# untitled.net
KiCad netlist of a schematic drawn in EAGLE
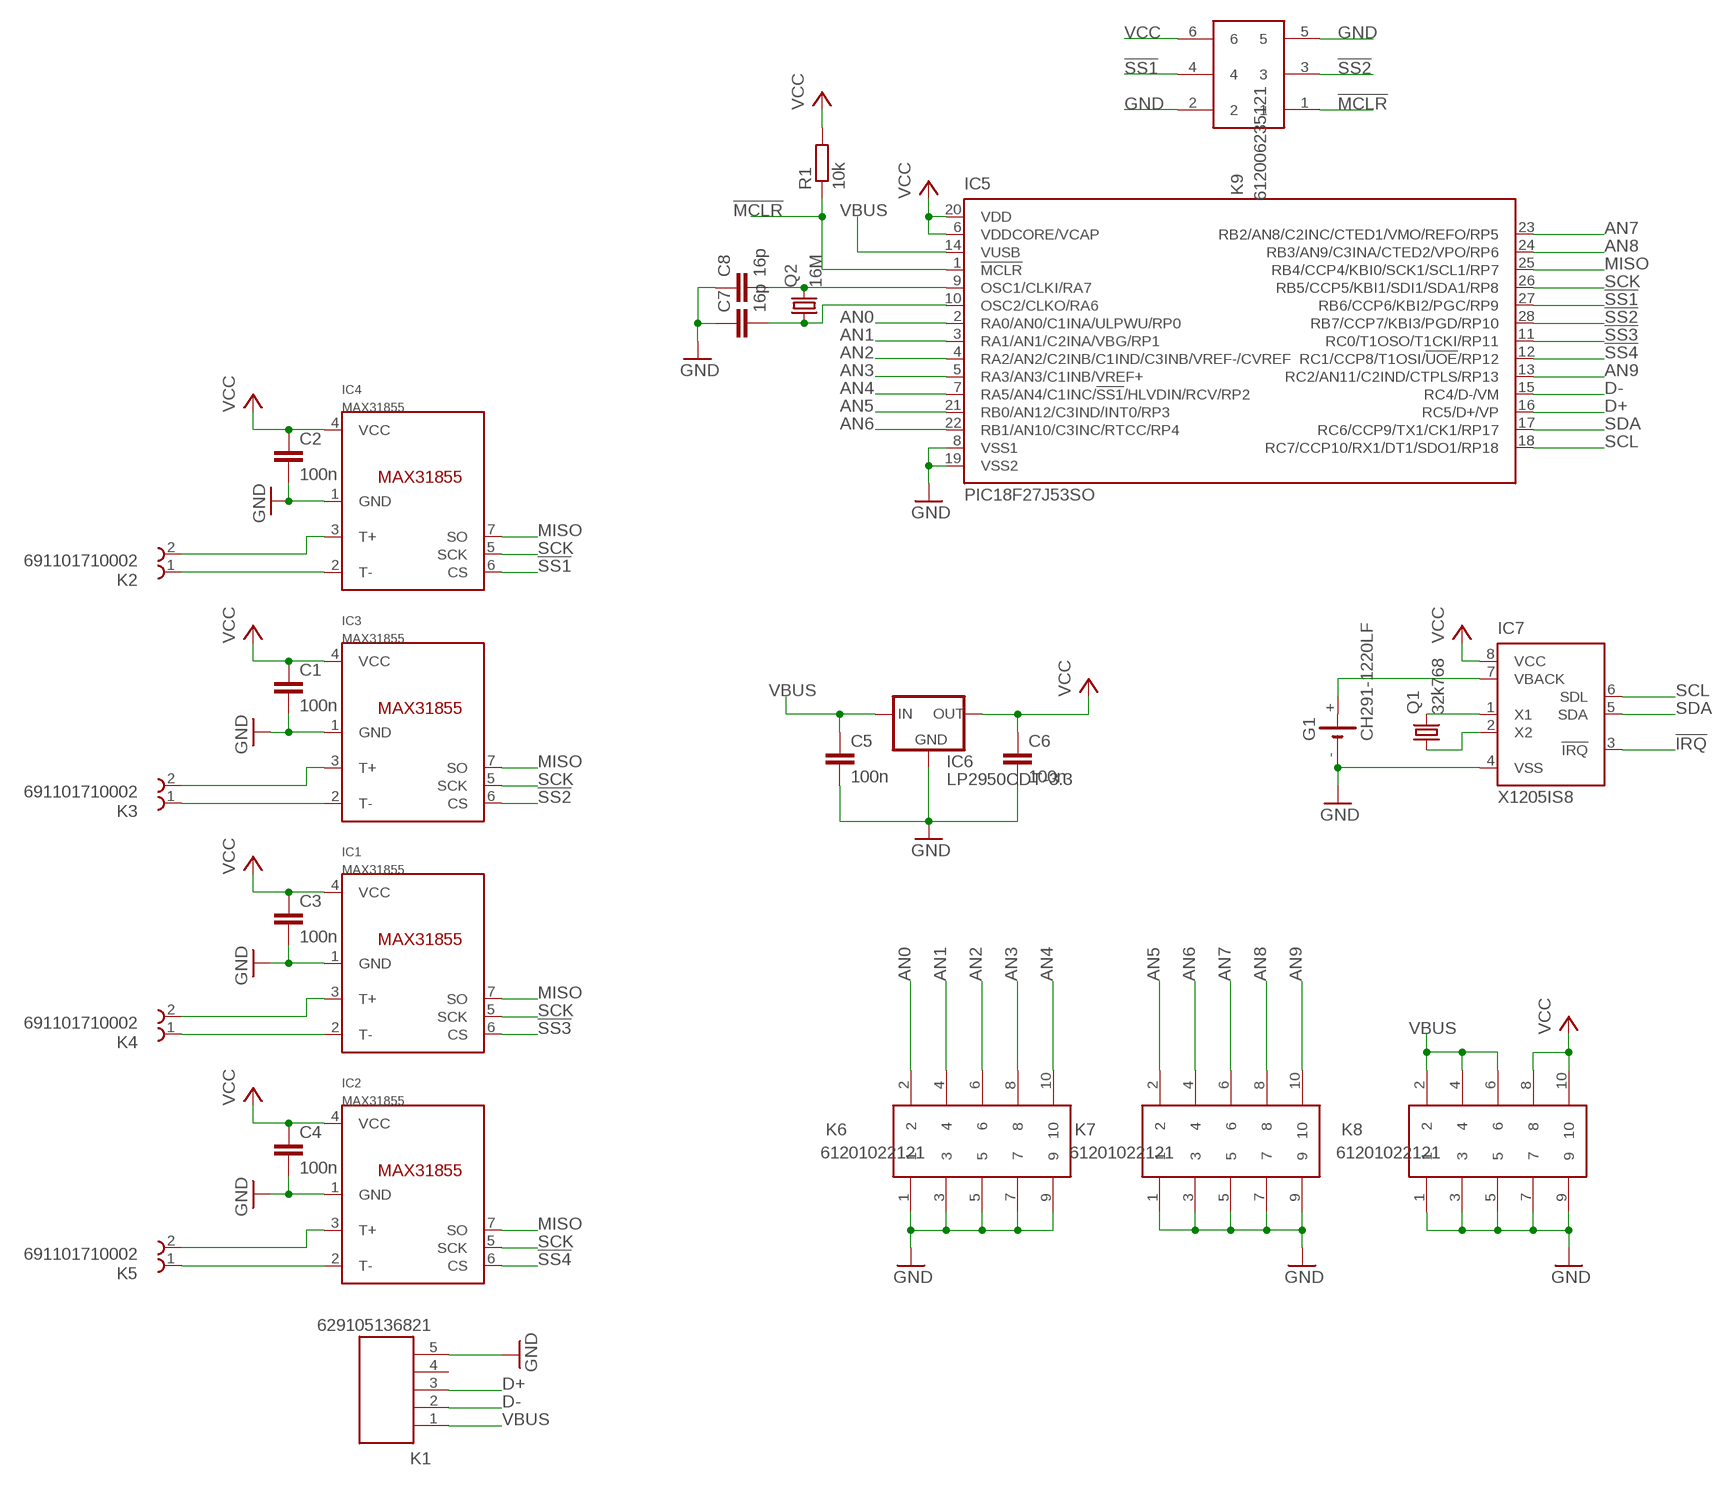
[diagram p0: schematic, sheet 1]

(export (version "E")
  (design (tool "Eeschema 10.0.6"))
  (components
    (comp (ref "C1")
      (value "100n")
      (footprint "eagle-import:C1206")
      (libsource (lib "eagle-import") (part "C-EUC1206"))
    )
    (comp (ref "C2")
      (value "100n")
      (footprint "eagle-import:C1206")
      (libsource (lib "eagle-import") (part "C-EUC1206"))
    )
    (comp (ref "C3")
      (value "100n")
      (footprint "eagle-import:C1206")
      (libsource (lib "eagle-import") (part "C-EUC1206"))
    )
    (comp (ref "C4")
      (value "100n")
      (footprint "eagle-import:C1206")
      (libsource (lib "eagle-import") (part "C-EUC1206"))
    )
    (comp (ref "C5")
      (value "100n")
      (footprint "eagle-import:C1206")
      (libsource (lib "eagle-import") (part "C-EUC1206"))
    )
    (comp (ref "C6")
      (value "100n")
      (footprint "eagle-import:C1206")
      (libsource (lib "eagle-import") (part "C-EUC1206"))
    )
    (comp (ref "C7")
      (value "16p")
      (footprint "eagle-import:C0805")
      (libsource (lib "eagle-import") (part "C-EUC0805"))
    )
    (comp (ref "C8")
      (value "16p")
      (footprint "eagle-import:C0805")
      (libsource (lib "eagle-import") (part "C-EUC0805"))
    )
    (comp (ref "G1")
      (value "CH291-1220LF")
      (footprint "eagle-import:CH291-1220LF")
      (libsource (lib "eagle-import") (part "CH291-1220LF"))
    )
    (comp (ref "IC1")
      (value "MAX31855")
      (footprint "eagle-import:SOIC8")
      (libsource (lib "eagle-import") (part "MAX31855"))
    )
    (comp (ref "IC2")
      (value "MAX31855")
      (footprint "eagle-import:SOIC8")
      (libsource (lib "eagle-import") (part "MAX31855"))
    )
    (comp (ref "IC3")
      (value "MAX31855")
      (footprint "eagle-import:SOIC8")
      (libsource (lib "eagle-import") (part "MAX31855"))
    )
    (comp (ref "IC4")
      (value "MAX31855")
      (footprint "eagle-import:SOIC8")
      (libsource (lib "eagle-import") (part "MAX31855"))
    )
    (comp (ref "IC5")
      (value "PIC18F27J53SO")
      (footprint "eagle-import:SO28W")
      (fields (field (name "MPN") "PIC18F27J53-I/SO"))
      (libsource (lib "eagle-import") (part "PIC18F2J53SO7"))
    )
    (comp (ref "IC6")
      (value "LP2950CDT-3.3")
      (footprint "eagle-import:DPACK")
      (libsource (lib "eagle-import") (part "LP2950?CDT-3.3"))
    )
    (comp (ref "IC7")
      (value "X1205IS8")
      (footprint "eagle-import:SO-08")
      (libsource (lib "eagle-import") (part "X1205S8I"))
    )
    (comp (ref "K1")
      (value "629105136821")
      (footprint "eagle-import:629105136821")
      (libsource (lib "eagle-import") (part "629105136821"))
    )
    (comp (ref "K2")
      (value "691101710002")
      (footprint "eagle-import:691101710002")
      (libsource (lib "eagle-import") (part "691101710002"))
    )
    (comp (ref "K3")
      (value "691101710002")
      (footprint "eagle-import:691101710002")
      (libsource (lib "eagle-import") (part "691101710002"))
    )
    (comp (ref "K4")
      (value "691101710002")
      (footprint "eagle-import:691101710002")
      (libsource (lib "eagle-import") (part "691101710002"))
    )
    (comp (ref "K5")
      (value "691101710002")
      (footprint "eagle-import:691101710002")
      (libsource (lib "eagle-import") (part "691101710002"))
    )
    (comp (ref "K6")
      (value "61201022121")
      (footprint "eagle-import:61201022121")
      (libsource (lib "eagle-import") (part "61201022121"))
    )
    (comp (ref "K7")
      (value "61201022121")
      (footprint "eagle-import:61201022121")
      (libsource (lib "eagle-import") (part "61201022121"))
    )
    (comp (ref "K8")
      (value "61201022121")
      (footprint "eagle-import:61201022121")
      (libsource (lib "eagle-import") (part "61201022121"))
    )
    (comp (ref "K9")
      (value "612006235121")
      (footprint "eagle-import:612006235121")
      (libsource (lib "eagle-import") (part "612006235121"))
    )
    (comp (ref "Q1")
      (value "32k768")
      (footprint "eagle-import:TC26H")
      (libsource (lib "eagle-import") (part "CRYSTALTC26H"))
    )
    (comp (ref "Q2")
      (value "16M")
      (footprint "eagle-import:CTS406")
      (libsource (lib "eagle-import") (part "CRYSTALCTS406"))
    )
    (comp (ref "R1")
      (value "10k")
      (footprint "eagle-import:M1206")
      (libsource (lib "eagle-import") (part "R-EU_M1206"))
    )
  )
  (nets
    (net (code "1") (name "/AN0") (class "Default")
      (node (ref "IC5") (pin "2") (pinfunction "RA0/AN0/C1INA/ULPWU/RP0_2") (pintype "bidirectional"))
      (node (ref "K6") (pin "2") (pinfunction "2_2") (pintype "passive"))
    )
    (net (code "2") (name "/AN1") (class "Default")
      (node (ref "IC5") (pin "3") (pinfunction "RA1/AN1/C2INA/VBG/RP1_3") (pintype "bidirectional"))
      (node (ref "K6") (pin "4") (pinfunction "4_4") (pintype "passive"))
    )
    (net (code "3") (name "/AN2") (class "Default")
      (node (ref "IC5") (pin "4") (pinfunction "RA2/AN2/C2INB/C1IND/C3INB/VREF-/CVREF_4") (pintype "bidirectional"))
      (node (ref "K6") (pin "6") (pinfunction "6_6") (pintype "passive"))
    )
    (net (code "4") (name "/AN3") (class "Default")
      (node (ref "IC5") (pin "5") (pinfunction "RA3/AN3/C1INB/VREF+_5") (pintype "bidirectional"))
      (node (ref "K6") (pin "8") (pinfunction "8_8") (pintype "passive"))
    )
    (net (code "5") (name "/AN4") (class "Default")
      (node (ref "IC5") (pin "7") (pinfunction "RA5/AN4/C1INC/~{SS1}/HLVDIN/RCV/RP2_7") (pintype "bidirectional"))
      (node (ref "K6") (pin "10") (pinfunction "10_10") (pintype "passive"))
    )
    (net (code "6") (name "/AN5") (class "Default")
      (node (ref "IC5") (pin "21") (pinfunction "RB0/AN12/C3IND/INT0/RP3_21") (pintype "bidirectional"))
      (node (ref "K7") (pin "2") (pinfunction "2_2") (pintype "passive"))
    )
    (net (code "7") (name "/AN6") (class "Default")
      (node (ref "IC5") (pin "22") (pinfunction "RB1/AN10/C3INC/RTCC/RP4_22") (pintype "bidirectional"))
      (node (ref "K7") (pin "4") (pinfunction "4_4") (pintype "passive"))
    )
    (net (code "8") (name "/AN7") (class "Default")
      (node (ref "IC5") (pin "23") (pinfunction "RB2/AN8/C2INC/CTED1/VMO/REFO/RP5_23") (pintype "bidirectional"))
      (node (ref "K7") (pin "6") (pinfunction "6_6") (pintype "passive"))
    )
    (net (code "9") (name "/AN8") (class "Default")
      (node (ref "IC5") (pin "24") (pinfunction "RB3/AN9/C3INA/CTED2/VPO/RP6_24") (pintype "bidirectional"))
      (node (ref "K7") (pin "8") (pinfunction "8_8") (pintype "passive"))
    )
    (net (code "10") (name "/AN9") (class "Default")
      (node (ref "IC5") (pin "13") (pinfunction "RC2/AN11/C2IND/CTPLS/RP13_13") (pintype "bidirectional"))
      (node (ref "K7") (pin "10") (pinfunction "10_10") (pintype "passive"))
    )
    (net (code "11") (name "/D+") (class "Default")
      (node (ref "IC5") (pin "16") (pinfunction "RC5/D+/VP_16") (pintype "bidirectional"))
      (node (ref "K1") (pin "3") (pinfunction "3_3") (pintype "passive"))
    )
    (net (code "12") (name "/D-") (class "Default")
      (node (ref "IC5") (pin "15") (pinfunction "RC4/D-/VM_15") (pintype "bidirectional"))
      (node (ref "K1") (pin "2") (pinfunction "2_2") (pintype "passive"))
    )
    (net (code "13") (name "/MISO") (class "Default")
      (node (ref "IC1") (pin "7") (pinfunction "SO_7") (pintype "output"))
      (node (ref "IC2") (pin "7") (pinfunction "SO_7") (pintype "output"))
      (node (ref "IC3") (pin "7") (pinfunction "SO_7") (pintype "output"))
      (node (ref "IC4") (pin "7") (pinfunction "SO_7") (pintype "output"))
      (node (ref "IC5") (pin "25") (pinfunction "RB4/CCP4/KBI0/SCK1/SCL1/RP7_25") (pintype "bidirectional"))
    )
    (net (code "14") (name "/SCK") (class "Default")
      (node (ref "IC1") (pin "5") (pinfunction "SCK_5") (pintype "input"))
      (node (ref "IC2") (pin "5") (pinfunction "SCK_5") (pintype "input"))
      (node (ref "IC3") (pin "5") (pinfunction "SCK_5") (pintype "input"))
      (node (ref "IC4") (pin "5") (pinfunction "SCK_5") (pintype "input"))
      (node (ref "IC5") (pin "26") (pinfunction "RB5/CCP5/KBI1/SDI1/SDA1/RP8_26") (pintype "bidirectional"))
    )
    (net (code "15") (name "/SCL") (class "Default")
      (node (ref "IC5") (pin "18") (pinfunction "RC7/CCP10/RX1/DT1/SDO1/RP18_18") (pintype "bidirectional"))
      (node (ref "IC7") (pin "6") (pinfunction "SDL_6") (pintype "input"))
    )
    (net (code "16") (name "/SDA") (class "Default")
      (node (ref "IC5") (pin "17") (pinfunction "RC6/CCP9/TX1/CK1/RP17_17") (pintype "bidirectional"))
      (node (ref "IC7") (pin "5") (pinfunction "SDA_5") (pintype "bidirectional"))
    )
    (net (code "17") (name "/VBUS") (class "Default")
      (node (ref "C5") (pin "1") (pinfunction "1_1") (pintype "passive"))
      (node (ref "IC5") (pin "14") (pinfunction "VUSB_14") (pintype "input"))
      (node (ref "IC6") (pin "1") (pinfunction "IN_1") (pintype "input"))
      (node (ref "K1") (pin "1") (pinfunction "1_1") (pintype "passive"))
      (node (ref "K8") (pin "2") (pinfunction "2_2") (pintype "passive"))
      (node (ref "K8") (pin "4") (pinfunction "4_4") (pintype "passive"))
      (node (ref "K8") (pin "6") (pinfunction "6_6") (pintype "passive"))
    )
    (net (code "18") (name "/~{IRQ}") (class "Default")
      (node (ref "IC7") (pin "3") (pinfunction "~{IRQ}_3") (pintype "output"))
    )
    (net (code "19") (name "/~{MCLR}") (class "Default")
      (node (ref "IC5") (pin "1") (pinfunction "~{MCLR}_1") (pintype "input"))
      (node (ref "K9") (pin "1") (pinfunction "1_1") (pintype "passive"))
      (node (ref "R1") (pin "1") (pinfunction "1_1") (pintype "passive"))
    )
    (net (code "20") (name "/~{SS1}") (class "Default")
      (node (ref "IC4") (pin "6") (pinfunction "CS_6") (pintype "input"))
      (node (ref "IC5") (pin "27") (pinfunction "RB6/CCP6/KBI2/PGC/RP9_27") (pintype "bidirectional"))
      (node (ref "K9") (pin "4") (pinfunction "4_4") (pintype "passive"))
    )
    (net (code "21") (name "/~{SS2}") (class "Default")
      (node (ref "IC3") (pin "6") (pinfunction "CS_6") (pintype "input"))
      (node (ref "IC5") (pin "28") (pinfunction "RB7/CCP7/KBI3/PGD/RP10_28") (pintype "bidirectional"))
      (node (ref "K9") (pin "3") (pinfunction "3_3") (pintype "passive"))
    )
    (net (code "22") (name "/~{SS3}") (class "Default")
      (node (ref "IC1") (pin "6") (pinfunction "CS_6") (pintype "input"))
      (node (ref "IC5") (pin "11") (pinfunction "RC0/T1OSO/T1CKI/RP11_11") (pintype "bidirectional"))
    )
    (net (code "23") (name "/~{SS4}") (class "Default")
      (node (ref "IC2") (pin "6") (pinfunction "CS_6") (pintype "input"))
      (node (ref "IC5") (pin "12") (pinfunction "RC1/CCP8/T1OSI/~{UOE}/RP12_12") (pintype "bidirectional"))
    )
    (net (code "24") (name "GND") (class "Default")
      (node (ref "C1") (pin "2") (pinfunction "2_2") (pintype "passive"))
      (node (ref "C2") (pin "2") (pinfunction "2_2") (pintype "passive"))
      (node (ref "C3") (pin "2") (pinfunction "2_2") (pintype "passive"))
      (node (ref "C4") (pin "2") (pinfunction "2_2") (pintype "passive"))
      (node (ref "C5") (pin "2") (pinfunction "2_2") (pintype "passive"))
      (node (ref "C6") (pin "2") (pinfunction "2_2") (pintype "passive"))
      (node (ref "C7") (pin "1") (pinfunction "1_1") (pintype "passive"))
      (node (ref "C8") (pin "1") (pinfunction "1_1") (pintype "passive"))
      (node (ref "G1") (pin "-") (pinfunction "-_-") (pintype "passive"))
      (node (ref "IC1") (pin "1") (pinfunction "GND_1") (pintype "power_in"))
      (node (ref "IC2") (pin "1") (pinfunction "GND_1") (pintype "power_in"))
      (node (ref "IC3") (pin "1") (pinfunction "GND_1") (pintype "power_in"))
      (node (ref "IC4") (pin "1") (pinfunction "GND_1") (pintype "power_in"))
      (node (ref "IC5") (pin "19") (pinfunction "VSS2_19") (pintype "input"))
      (node (ref "IC5") (pin "8") (pinfunction "VSS1_8") (pintype "input"))
      (node (ref "IC6") (pin "4") (pinfunction "GND_4") (pintype "input"))
      (node (ref "IC7") (pin "4") (pinfunction "VSS_4") (pintype "power_in"))
      (node (ref "K1") (pin "5") (pinfunction "5_5") (pintype "passive"))
      (node (ref "K6") (pin "1") (pinfunction "1_1") (pintype "passive"))
      (node (ref "K6") (pin "3") (pinfunction "3_3") (pintype "passive"))
      (node (ref "K6") (pin "5") (pinfunction "5_5") (pintype "passive"))
      (node (ref "K6") (pin "7") (pinfunction "7_7") (pintype "passive"))
      (node (ref "K6") (pin "9") (pinfunction "9_9") (pintype "passive"))
      (node (ref "K7") (pin "1") (pinfunction "1_1") (pintype "passive"))
      (node (ref "K7") (pin "3") (pinfunction "3_3") (pintype "passive"))
      (node (ref "K7") (pin "5") (pinfunction "5_5") (pintype "passive"))
      (node (ref "K7") (pin "7") (pinfunction "7_7") (pintype "passive"))
      (node (ref "K7") (pin "9") (pinfunction "9_9") (pintype "passive"))
      (node (ref "K8") (pin "1") (pinfunction "1_1") (pintype "passive"))
      (node (ref "K8") (pin "3") (pinfunction "3_3") (pintype "passive"))
      (node (ref "K8") (pin "5") (pinfunction "5_5") (pintype "passive"))
      (node (ref "K8") (pin "7") (pinfunction "7_7") (pintype "passive"))
      (node (ref "K8") (pin "9") (pinfunction "9_9") (pintype "passive"))
      (node (ref "K9") (pin "2") (pinfunction "2_2") (pintype "passive"))
      (node (ref "K9") (pin "5") (pinfunction "5_5") (pintype "passive"))
    )
    (net (code "25") (name "Net-(IC1-T+)") (class "Default")
      (node (ref "IC1") (pin "3") (pinfunction "T+_3") (pintype "input"))
      (node (ref "K4") (pin "2") (pinfunction "2_2") (pintype "passive"))
    )
    (net (code "26") (name "Net-(IC1-T-)") (class "Default")
      (node (ref "IC1") (pin "2") (pinfunction "T-_2") (pintype "input"))
      (node (ref "K4") (pin "1") (pinfunction "1_1") (pintype "passive"))
    )
    (net (code "27") (name "Net-(IC2-T+)") (class "Default")
      (node (ref "IC2") (pin "3") (pinfunction "T+_3") (pintype "input"))
      (node (ref "K5") (pin "2") (pinfunction "2_2") (pintype "passive"))
    )
    (net (code "28") (name "Net-(IC2-T-)") (class "Default")
      (node (ref "IC2") (pin "2") (pinfunction "T-_2") (pintype "input"))
      (node (ref "K5") (pin "1") (pinfunction "1_1") (pintype "passive"))
    )
    (net (code "29") (name "Net-(IC3-T+)") (class "Default")
      (node (ref "IC3") (pin "3") (pinfunction "T+_3") (pintype "input"))
      (node (ref "K3") (pin "2") (pinfunction "2_2") (pintype "passive"))
    )
    (net (code "30") (name "Net-(IC3-T-)") (class "Default")
      (node (ref "IC3") (pin "2") (pinfunction "T-_2") (pintype "input"))
      (node (ref "K3") (pin "1") (pinfunction "1_1") (pintype "passive"))
    )
    (net (code "31") (name "Net-(IC4-T+)") (class "Default")
      (node (ref "IC4") (pin "3") (pinfunction "T+_3") (pintype "input"))
      (node (ref "K2") (pin "2") (pinfunction "2_2") (pintype "passive"))
    )
    (net (code "32") (name "Net-(IC4-T-)") (class "Default")
      (node (ref "IC4") (pin "2") (pinfunction "T-_2") (pintype "input"))
      (node (ref "K2") (pin "1") (pinfunction "1_1") (pintype "passive"))
    )
    (net (code "33") (name "Net-(IC5-OSC1{slash}CLKI{slash}RA7)") (class "Default")
      (node (ref "C8") (pin "2") (pinfunction "2_2") (pintype "passive"))
      (node (ref "IC5") (pin "9") (pinfunction "OSC1/CLKI/RA7_9") (pintype "bidirectional"))
      (node (ref "Q2") (pin "3") (pinfunction "2_3") (pintype "passive"))
    )
    (net (code "34") (name "Net-(IC5-OSC2{slash}CLKO{slash}RA6)") (class "Default")
      (node (ref "C7") (pin "2") (pinfunction "2_2") (pintype "passive"))
      (node (ref "IC5") (pin "10") (pinfunction "OSC2/CLKO/RA6_10") (pintype "bidirectional"))
      (node (ref "Q2") (pin "1") (pinfunction "1_1") (pintype "passive"))
    )
    (net (code "35") (name "Net-(IC7-VBACK)") (class "Default")
      (node (ref "G1") (pin "+") (pinfunction "+_+") (pintype "passive"))
      (node (ref "IC7") (pin "7") (pinfunction "VBACK_7") (pintype "input"))
    )
    (net (code "36") (name "Net-(IC7-X1)") (class "Default")
      (node (ref "IC7") (pin "1") (pinfunction "X1_1") (pintype "input"))
      (node (ref "Q1") (pin "2") (pinfunction "2_2") (pintype "passive"))
    )
    (net (code "37") (name "Net-(IC7-X2)") (class "Default")
      (node (ref "IC7") (pin "2") (pinfunction "X2_2") (pintype "output"))
      (node (ref "Q1") (pin "1") (pinfunction "1_1") (pintype "passive"))
    )
    (net (code "38") (name "VCC") (class "Default")
      (node (ref "C1") (pin "1") (pinfunction "1_1") (pintype "passive"))
      (node (ref "C2") (pin "1") (pinfunction "1_1") (pintype "passive"))
      (node (ref "C3") (pin "1") (pinfunction "1_1") (pintype "passive"))
      (node (ref "C4") (pin "1") (pinfunction "1_1") (pintype "passive"))
      (node (ref "C6") (pin "1") (pinfunction "1_1") (pintype "passive"))
      (node (ref "IC1") (pin "4") (pinfunction "VCC_4") (pintype "power_in"))
      (node (ref "IC2") (pin "4") (pinfunction "VCC_4") (pintype "power_in"))
      (node (ref "IC3") (pin "4") (pinfunction "VCC_4") (pintype "power_in"))
      (node (ref "IC4") (pin "4") (pinfunction "VCC_4") (pintype "power_in"))
      (node (ref "IC5") (pin "20") (pinfunction "VDD_20") (pintype "input"))
      (node (ref "IC5") (pin "6") (pinfunction "VDDCORE/VCAP_6") (pintype "input"))
      (node (ref "IC6") (pin "3") (pinfunction "OUT_3") (pintype "passive"))
      (node (ref "IC7") (pin "8") (pinfunction "VCC_8") (pintype "power_in"))
      (node (ref "K8") (pin "10") (pinfunction "10_10") (pintype "passive"))
      (node (ref "K8") (pin "8") (pinfunction "8_8") (pintype "passive"))
      (node (ref "K9") (pin "6") (pinfunction "6_6") (pintype "passive"))
      (node (ref "R1") (pin "2") (pinfunction "2_2") (pintype "passive"))
    )
    (net (code "39") (name "unconnected-(K1-Pad4)") (class "Default")
      (node (ref "K1") (pin "4") (pinfunction "4_4") (pintype "passive"))
    )
  )
)
